# FT232R-Breakout.net
KiCad netlist of a schematic drawn in EAGLE
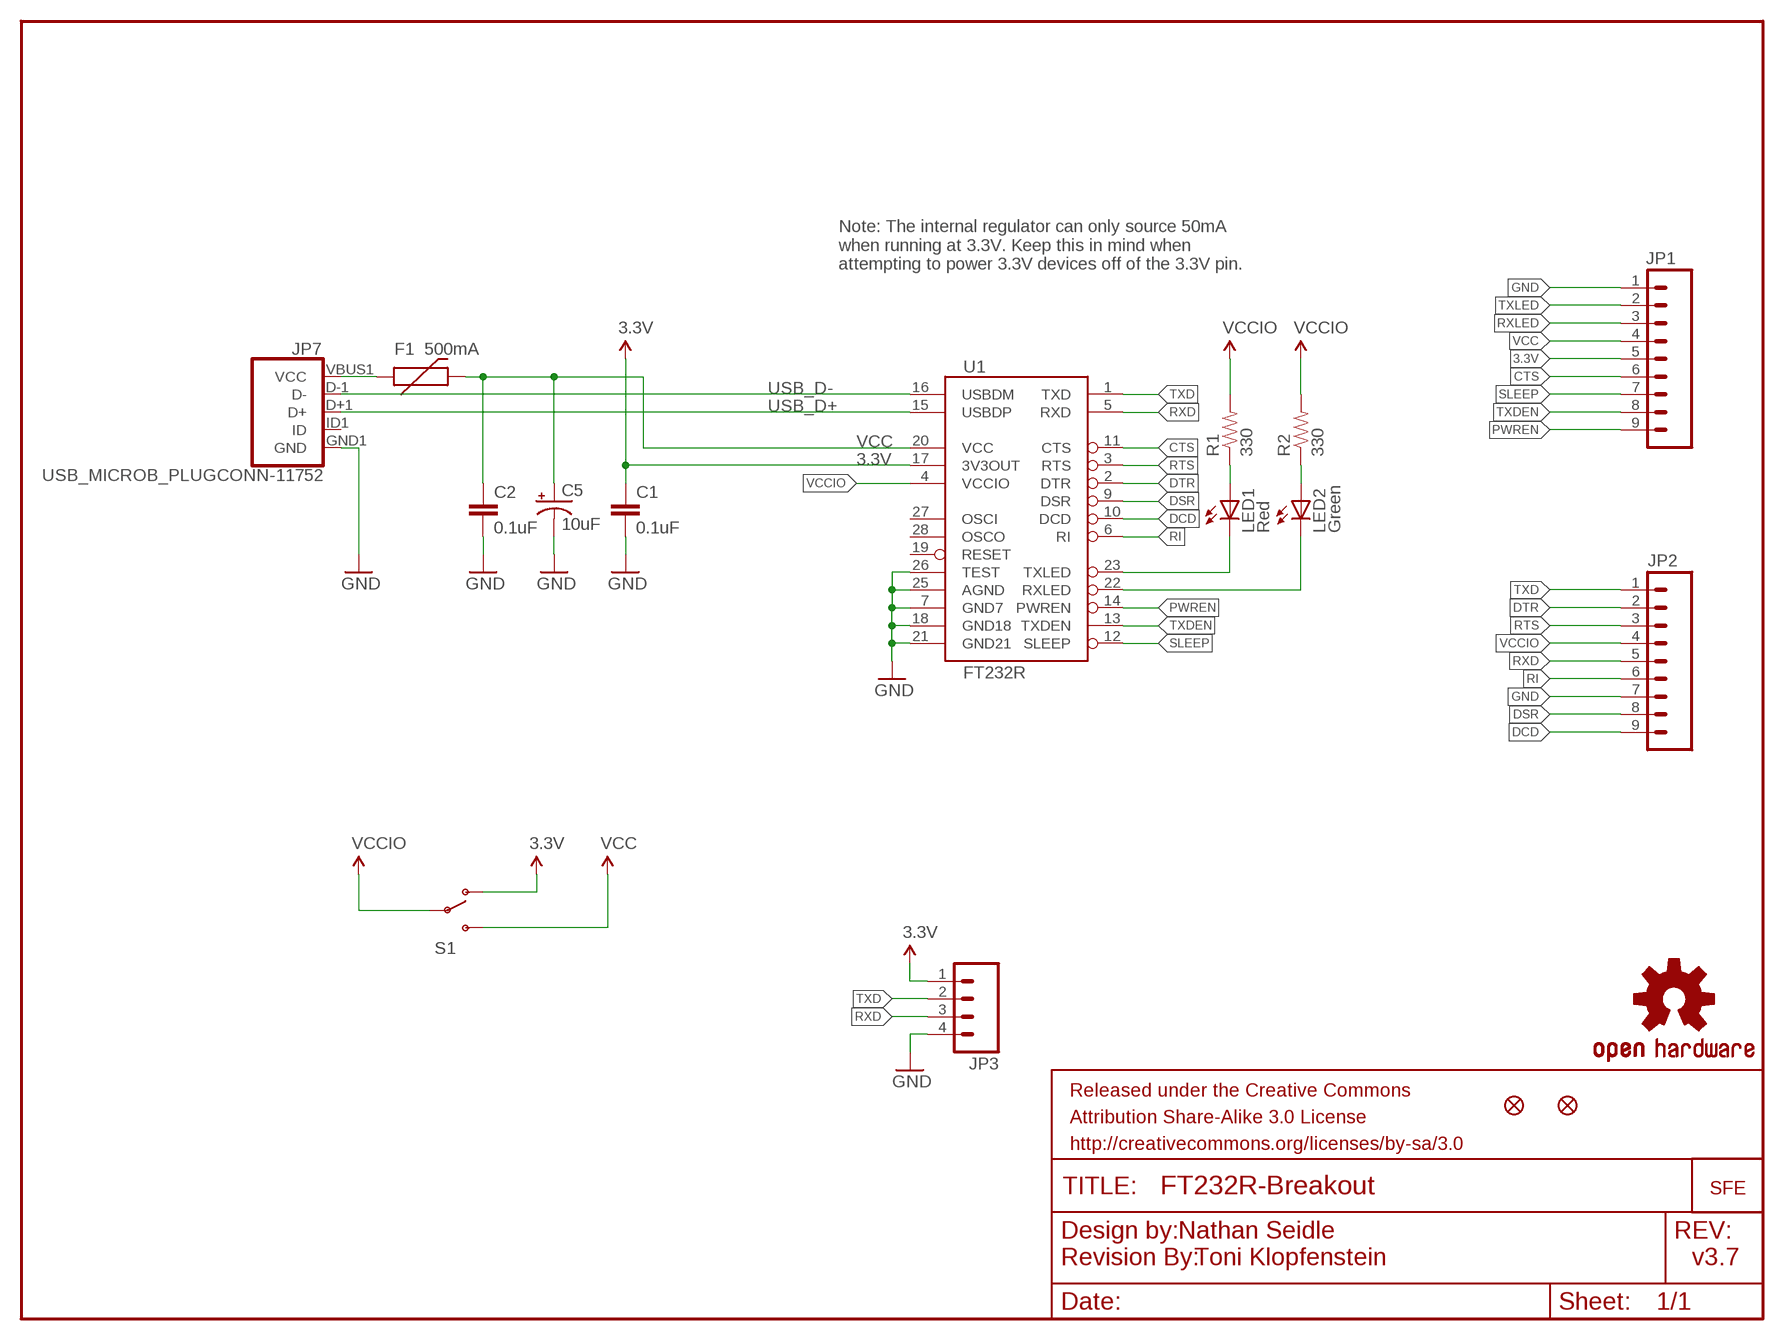
[diagram p0: schematic, sheet 1]

(export (version "E")
  (design (tool "Eeschema 10.0.6"))
  (components
    (comp (ref "C1")
      (value "0.1uF")
      (footprint "eagle-import:0603-CAP")
      (libsource (lib "eagle-import") (part "0.1UF-25V(+80/-20%)(0603)"))
    )
    (comp (ref "C2")
      (value "0.1uF")
      (footprint "eagle-import:0603-CAP")
      (libsource (lib "eagle-import") (part "0.1UF-25V(+80/-20%)(0603)"))
    )
    (comp (ref "C5")
      (value "10uF")
      (footprint "eagle-import:EIA3216")
      (libsource (lib "eagle-import") (part "10UF-16V-10%(TANT)"))
    )
    (comp (ref "F1")
      (value "500mA")
      (footprint "eagle-import:PTC-1206")
      (libsource (lib "eagle-import") (part "PTCSMD"))
    )
    (comp (ref "FRAME1")
      (value "FRAME-LETTER")
      (footprint "eagle-import:CREATIVE_COMMONS")
      (libsource (lib "eagle-import") (part "FRAME-LETTER"))
    )
    (comp (ref "JP1")
      (value "M09")
      (footprint "eagle-import:1X09")
      (libsource (lib "eagle-import") (part "M09"))
    )
    (comp (ref "JP2")
      (value "M09")
      (footprint "eagle-import:1X09")
      (libsource (lib "eagle-import") (part "M09"))
    )
    (comp (ref "JP3")
      (value "M04PTH")
      (footprint "eagle-import:1X04")
      (libsource (lib "eagle-import") (part "M04PTH"))
    )
    (comp (ref "JP5")
      (value "FIDUCIAL1X2")
      (footprint "eagle-import:FIDUCIAL-1X2")
      (libsource (lib "eagle-import") (part "FIDUCIAL1X2"))
    )
    (comp (ref "JP6")
      (value "FIDUCIAL1X2")
      (footprint "eagle-import:FIDUCIAL-1X2")
      (libsource (lib "eagle-import") (part "FIDUCIAL1X2"))
    )
    (comp (ref "JP7")
      (value "USB_MICROB_PLUGCONN-11752")
      (footprint "eagle-import:USB-B-MICRO-SMD_V03")
      (libsource (lib "eagle-import") (part "USB_MICROB_PLUGCONN-11752"))
    )
    (comp (ref "LED1")
      (value "Red")
      (footprint "eagle-import:LED-0603")
      (libsource (lib "eagle-import") (part "LED-RED0603"))
    )
    (comp (ref "LED2")
      (value "Green")
      (footprint "eagle-import:LED-0603")
      (libsource (lib "eagle-import") (part "LED-GREEN0603"))
    )
    (comp (ref "LOGO1")
      (value "OSHW-LOGOS")
      (footprint "eagle-import:OSHW-LOGO-S")
      (libsource (lib "eagle-import") (part "OSHW-LOGOS"))
    )
    (comp (ref "R1")
      (value "330")
      (footprint "eagle-import:0603-RES")
      (libsource (lib "eagle-import") (part "330OHM1/10W1%(0603)"))
    )
    (comp (ref "R2")
      (value "330")
      (footprint "eagle-import:0603-RES")
      (libsource (lib "eagle-import") (part "330OHM1/10W1%(0603)"))
    )
    (comp (ref "S1")
      (value "SWITCH-SPDTSMD")
      (footprint "eagle-import:AYZ0202")
      (libsource (lib "eagle-import") (part "SWITCH-SPDTSMD"))
    )
    (comp (ref "U$1")
      (value "REVISION")
      (footprint "eagle-import:REVISION")
      (libsource (lib "eagle-import") (part "REVISION"))
    )
    (comp (ref "U$2")
      (value "LOGO-SFENEW")
      (footprint "eagle-import:SFE-NEW-WEBLOGO")
      (libsource (lib "eagle-import") (part "LOGO-SFENEW"))
    )
    (comp (ref "U1")
      (value "FT232R")
      (footprint "eagle-import:SSOP28DB")
      (libsource (lib "eagle-import") (part "FT232RLSSOP"))
    )
  )
  (nets
    (net (code "1") (name "/USB_D+") (class "Default")
      (node (ref "JP7") (pin "D+1") (pinfunction "D+_D+1") (pintype "bidirectional"))
      (node (ref "U1") (pin "15") (pinfunction "USBDP_15") (pintype "bidirectional"))
    )
    (net (code "2") (name "/USB_D-") (class "Default")
      (node (ref "JP7") (pin "D-1") (pinfunction "D-_D-1") (pintype "bidirectional"))
      (node (ref "U1") (pin "16") (pinfunction "USBDM_16") (pintype "bidirectional"))
    )
    (net (code "3") (name "3.3V") (class "Default")
      (node (ref "C1") (pin "1") (pinfunction "1_1") (pintype "passive"))
      (node (ref "JP1") (pin "5") (pinfunction "5_5") (pintype "passive"))
      (node (ref "JP3") (pin "1") (pinfunction "1_1") (pintype "passive"))
      (node (ref "S1") (pin "1") (pinfunction "O_1") (pintype "passive"))
      (node (ref "U1") (pin "17") (pinfunction "3V3OUT_17") (pintype "output"))
    )
    (net (code "4") (name "CTS") (class "Default")
      (node (ref "JP1") (pin "6") (pinfunction "6_6") (pintype "passive"))
      (node (ref "U1") (pin "11") (pinfunction "CTS_11") (pintype "input"))
    )
    (net (code "5") (name "DCD") (class "Default")
      (node (ref "JP2") (pin "9") (pinfunction "9_9") (pintype "passive"))
      (node (ref "U1") (pin "10") (pinfunction "DCD_10") (pintype "input"))
    )
    (net (code "6") (name "DSR") (class "Default")
      (node (ref "JP2") (pin "8") (pinfunction "8_8") (pintype "passive"))
      (node (ref "U1") (pin "9") (pinfunction "DSR_9") (pintype "input"))
    )
    (net (code "7") (name "DTR") (class "Default")
      (node (ref "JP2") (pin "2") (pinfunction "2_2") (pintype "passive"))
      (node (ref "U1") (pin "2") (pinfunction "DTR_2") (pintype "output"))
    )
    (net (code "8") (name "GND") (class "Default")
      (node (ref "C1") (pin "2") (pinfunction "2_2") (pintype "passive"))
      (node (ref "C2") (pin "2") (pinfunction "2_2") (pintype "passive"))
      (node (ref "C5") (pin "C") (pinfunction "-_C") (pintype "passive"))
      (node (ref "JP1") (pin "1") (pinfunction "1_1") (pintype "passive"))
      (node (ref "JP2") (pin "7") (pinfunction "7_7") (pintype "passive"))
      (node (ref "JP3") (pin "4") (pinfunction "4_4") (pintype "passive"))
      (node (ref "JP7") (pin "GND1") (pinfunction "GND_GND1") (pintype "bidirectional"))
      (node (ref "U1") (pin "18") (pinfunction "GND18_18") (pintype "power_in"))
      (node (ref "U1") (pin "21") (pinfunction "GND21_21") (pintype "power_in"))
      (node (ref "U1") (pin "25") (pinfunction "AGND_25") (pintype "power_in"))
      (node (ref "U1") (pin "26") (pinfunction "TEST_26") (pintype "input"))
      (node (ref "U1") (pin "7") (pinfunction "GND7_7") (pintype "power_in"))
    )
    (net (code "9") (name "Net-(JP7-VCC)") (class "Default")
      (node (ref "F1") (pin "1") (pinfunction "1_1") (pintype "bidirectional"))
      (node (ref "JP7") (pin "VBUS1") (pinfunction "VCC_VBUS1") (pintype "bidirectional"))
    )
    (net (code "10") (name "Net-(LED1-PadA)") (class "Default")
      (node (ref "LED1") (pin "A") (pinfunction "A_A") (pintype "passive"))
      (node (ref "R1") (pin "1") (pinfunction "1_1") (pintype "passive"))
    )
    (net (code "11") (name "Net-(LED2-PadA)") (class "Default")
      (node (ref "LED2") (pin "A") (pinfunction "A_A") (pintype "passive"))
      (node (ref "R2") (pin "1") (pinfunction "1_1") (pintype "passive"))
    )
    (net (code "12") (name "PWREN") (class "Default")
      (node (ref "JP1") (pin "9") (pinfunction "9_9") (pintype "passive"))
      (node (ref "U1") (pin "14") (pinfunction "PWREN_14") (pintype "input"))
    )
    (net (code "13") (name "RI") (class "Default")
      (node (ref "JP2") (pin "6") (pinfunction "6_6") (pintype "passive"))
      (node (ref "U1") (pin "6") (pinfunction "RI_6") (pintype "input"))
    )
    (net (code "14") (name "RTS") (class "Default")
      (node (ref "JP2") (pin "3") (pinfunction "3_3") (pintype "passive"))
      (node (ref "U1") (pin "3") (pinfunction "RTS_3") (pintype "output"))
    )
    (net (code "15") (name "RXD") (class "Default")
      (node (ref "JP2") (pin "5") (pinfunction "5_5") (pintype "passive"))
      (node (ref "JP3") (pin "3") (pinfunction "3_3") (pintype "passive"))
      (node (ref "U1") (pin "5") (pinfunction "RXD_5") (pintype "input"))
    )
    (net (code "16") (name "RXLED") (class "Default")
      (node (ref "JP1") (pin "3") (pinfunction "3_3") (pintype "passive"))
      (node (ref "LED2") (pin "C") (pinfunction "C_C") (pintype "passive"))
      (node (ref "U1") (pin "22") (pinfunction "RXLED_22") (pintype "input"))
    )
    (net (code "17") (name "SLEEP") (class "Default")
      (node (ref "JP1") (pin "7") (pinfunction "7_7") (pintype "passive"))
      (node (ref "U1") (pin "12") (pinfunction "SLEEP_12") (pintype "input"))
    )
    (net (code "18") (name "TXD") (class "Default")
      (node (ref "JP2") (pin "1") (pinfunction "1_1") (pintype "passive"))
      (node (ref "JP3") (pin "2") (pinfunction "2_2") (pintype "passive"))
      (node (ref "U1") (pin "1") (pinfunction "TXD_1") (pintype "output"))
    )
    (net (code "19") (name "TXDEN") (class "Default")
      (node (ref "JP1") (pin "8") (pinfunction "8_8") (pintype "passive"))
      (node (ref "U1") (pin "13") (pinfunction "TXDEN_13") (pintype "input"))
    )
    (net (code "20") (name "TXLED") (class "Default")
      (node (ref "JP1") (pin "2") (pinfunction "2_2") (pintype "passive"))
      (node (ref "LED1") (pin "C") (pinfunction "C_C") (pintype "passive"))
      (node (ref "U1") (pin "23") (pinfunction "TXLED_23") (pintype "input"))
    )
    (net (code "21") (name "VCC") (class "Default")
      (node (ref "C2") (pin "1") (pinfunction "1_1") (pintype "passive"))
      (node (ref "C5") (pin "A") (pinfunction "+_A") (pintype "passive"))
      (node (ref "F1") (pin "2") (pinfunction "2_2") (pintype "bidirectional"))
      (node (ref "JP1") (pin "4") (pinfunction "4_4") (pintype "passive"))
      (node (ref "S1") (pin "3") (pinfunction "S_3") (pintype "passive"))
      (node (ref "U1") (pin "20") (pinfunction "VCC_20") (pintype "power_in"))
    )
    (net (code "22") (name "VCCIO") (class "Default")
      (node (ref "JP2") (pin "4") (pinfunction "4_4") (pintype "passive"))
      (node (ref "R1") (pin "2") (pinfunction "2_2") (pintype "passive"))
      (node (ref "R2") (pin "2") (pinfunction "2_2") (pintype "passive"))
      (node (ref "S1") (pin "2") (pinfunction "P_2") (pintype "passive"))
      (node (ref "U1") (pin "4") (pinfunction "VCCIO_4") (pintype "power_in"))
    )
    (net (code "23") (name "unconnected-(JP7-ID-PadID1)") (class "Default")
      (node (ref "JP7") (pin "ID1") (pinfunction "ID_ID1") (pintype "bidirectional"))
    )
    (net (code "24") (name "unconnected-(U1-OSCI-Pad27)") (class "Default")
      (node (ref "U1") (pin "27") (pinfunction "OSCI_27") (pintype "input"))
    )
    (net (code "25") (name "unconnected-(U1-OSCO-Pad28)") (class "Default")
      (node (ref "U1") (pin "28") (pinfunction "OSCO_28") (pintype "output"))
    )
    (net (code "26") (name "unconnected-(U1-RESET-Pad19)") (class "Default")
      (node (ref "U1") (pin "19") (pinfunction "RESET_19") (pintype "input"))
    )
  )
)
